# NB2_PBCON.net
KiCad netlist of a schematic drawn in Altium Designer
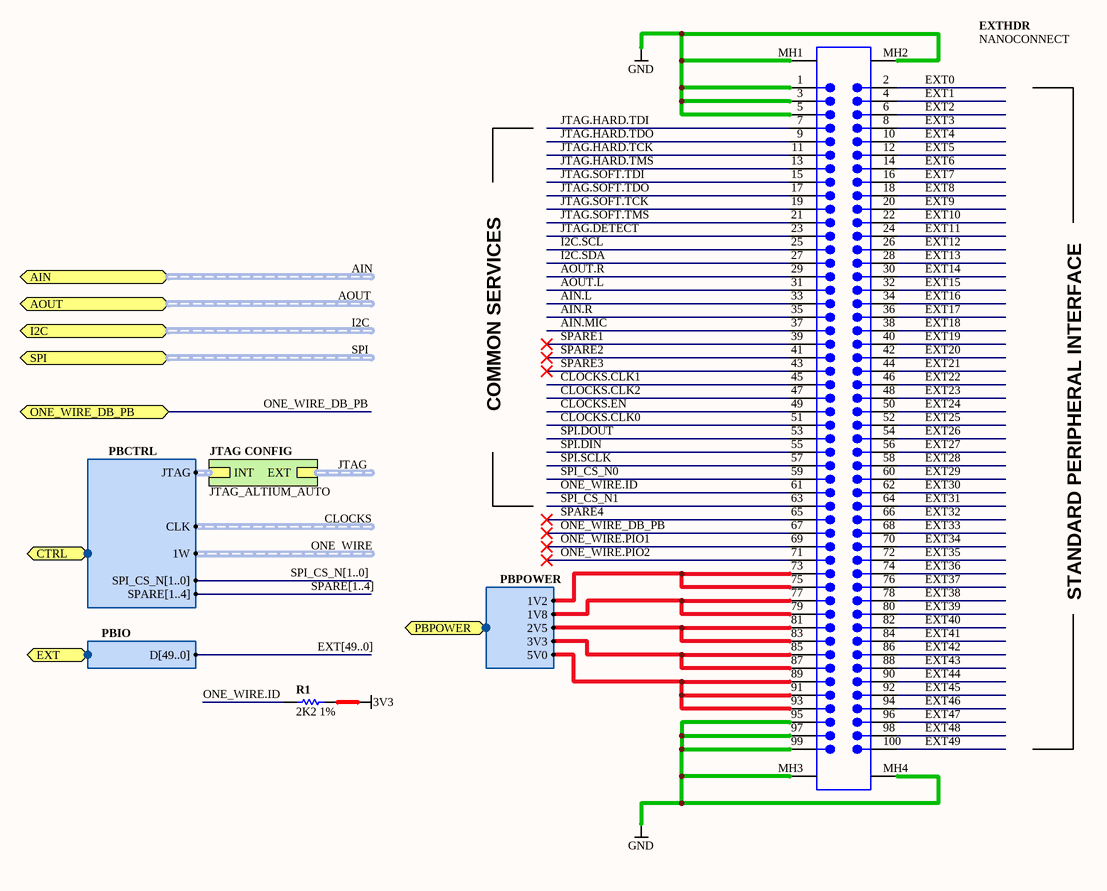
[diagram p0: NB2_PBCON.schdoc]

(export (version "E")
  (design (tool "Eeschema 10.0.6"))
  (components
    (comp (ref "EXTHDR")
      (value "NANOCONNECT")
      (footprint "53751")
      (description "Connector, Molex Docking Station 100 Pin Female 53751")
      (libsource (lib "altium-import") (part "root_0_CON-DOCKSTAT-100-F-STR_"))
    )
    (comp (ref "R1")
      (value "2K2 1%")
      (footprint "RESC1005-STAR")
      (description "Resistor, 2K2 1% 0402 (1005)")
      (fields (field (name "TOLERANCE") "1 %"))
      (libsource (lib "AltiumDesignLibrary") (part "RES"))
    )
  )
  (nets
    (net (code "11") (name "/AIN.L") (class "Default")
      (node (ref "EXTHDR") (pin "33") (pinfunction "33_33") (pintype "passive"))
    )
    (net (code "12") (name "/AIN.MIC") (class "Default")
      (node (ref "EXTHDR") (pin "37") (pinfunction "37_37") (pintype "passive"))
    )
    (net (code "13") (name "/AIN.R") (class "Default")
      (node (ref "EXTHDR") (pin "35") (pinfunction "35_35") (pintype "passive"))
    )
    (net (code "14") (name "/AOUT.L") (class "Default")
      (node (ref "EXTHDR") (pin "31") (pinfunction "31_31") (pintype "passive"))
    )
    (net (code "15") (name "/AOUT.R") (class "Default")
      (node (ref "EXTHDR") (pin "29") (pinfunction "29_29") (pintype "passive"))
    )
    (net (code "16") (name "/CLOCKS.CLK0") (class "Default")
      (node (ref "EXTHDR") (pin "51") (pinfunction "51_51") (pintype "passive"))
    )
    (net (code "17") (name "/CLOCKS.CLK1") (class "Default")
      (node (ref "EXTHDR") (pin "45") (pinfunction "45_45") (pintype "passive"))
    )
    (net (code "18") (name "/CLOCKS.CLK2") (class "Default")
      (node (ref "EXTHDR") (pin "47") (pinfunction "47_47") (pintype "passive"))
    )
    (net (code "19") (name "/CLOCKS.EN") (class "Default")
      (node (ref "EXTHDR") (pin "49") (pinfunction "49_49") (pintype "passive"))
    )
    (net (code "21") (name "/EXT0") (class "Default")
      (node (ref "EXTHDR") (pin "2") (pinfunction "2_2") (pintype "passive"))
    )
    (net (code "22") (name "/EXT1") (class "Default")
      (node (ref "EXTHDR") (pin "4") (pinfunction "4_4") (pintype "passive"))
    )
    (net (code "23") (name "/EXT2") (class "Default")
      (node (ref "EXTHDR") (pin "6") (pinfunction "6_6") (pintype "passive"))
    )
    (net (code "24") (name "/EXT3") (class "Default")
      (node (ref "EXTHDR") (pin "8") (pinfunction "8_8") (pintype "passive"))
    )
    (net (code "25") (name "/EXT4") (class "Default")
      (node (ref "EXTHDR") (pin "10") (pinfunction "10_10") (pintype "passive"))
    )
    (net (code "26") (name "/EXT5") (class "Default")
      (node (ref "EXTHDR") (pin "12") (pinfunction "12_12") (pintype "passive"))
    )
    (net (code "27") (name "/EXT6") (class "Default")
      (node (ref "EXTHDR") (pin "14") (pinfunction "14_14") (pintype "passive"))
    )
    (net (code "28") (name "/EXT7") (class "Default")
      (node (ref "EXTHDR") (pin "16") (pinfunction "16_16") (pintype "passive"))
    )
    (net (code "29") (name "/EXT8") (class "Default")
      (node (ref "EXTHDR") (pin "18") (pinfunction "18_18") (pintype "passive"))
    )
    (net (code "30") (name "/EXT9") (class "Default")
      (node (ref "EXTHDR") (pin "20") (pinfunction "20_20") (pintype "passive"))
    )
    (net (code "31") (name "/EXT10") (class "Default")
      (node (ref "EXTHDR") (pin "22") (pinfunction "22_22") (pintype "passive"))
    )
    (net (code "32") (name "/EXT11") (class "Default")
      (node (ref "EXTHDR") (pin "24") (pinfunction "24_24") (pintype "passive"))
    )
    (net (code "33") (name "/EXT12") (class "Default")
      (node (ref "EXTHDR") (pin "26") (pinfunction "26_26") (pintype "passive"))
    )
    (net (code "34") (name "/EXT13") (class "Default")
      (node (ref "EXTHDR") (pin "28") (pinfunction "28_28") (pintype "passive"))
    )
    (net (code "35") (name "/EXT14") (class "Default")
      (node (ref "EXTHDR") (pin "30") (pinfunction "30_30") (pintype "passive"))
    )
    (net (code "36") (name "/EXT15") (class "Default")
      (node (ref "EXTHDR") (pin "32") (pinfunction "32_32") (pintype "passive"))
    )
    (net (code "37") (name "/EXT16") (class "Default")
      (node (ref "EXTHDR") (pin "34") (pinfunction "34_34") (pintype "passive"))
    )
    (net (code "38") (name "/EXT17") (class "Default")
      (node (ref "EXTHDR") (pin "36") (pinfunction "36_36") (pintype "passive"))
    )
    (net (code "39") (name "/EXT18") (class "Default")
      (node (ref "EXTHDR") (pin "38") (pinfunction "38_38") (pintype "passive"))
    )
    (net (code "40") (name "/EXT19") (class "Default")
      (node (ref "EXTHDR") (pin "40") (pinfunction "40_40") (pintype "passive"))
    )
    (net (code "41") (name "/EXT20") (class "Default")
      (node (ref "EXTHDR") (pin "42") (pinfunction "42_42") (pintype "passive"))
    )
    (net (code "42") (name "/EXT21") (class "Default")
      (node (ref "EXTHDR") (pin "44") (pinfunction "44_44") (pintype "passive"))
    )
    (net (code "43") (name "/EXT22") (class "Default")
      (node (ref "EXTHDR") (pin "46") (pinfunction "46_46") (pintype "passive"))
    )
    (net (code "44") (name "/EXT23") (class "Default")
      (node (ref "EXTHDR") (pin "48") (pinfunction "48_48") (pintype "passive"))
    )
    (net (code "45") (name "/EXT24") (class "Default")
      (node (ref "EXTHDR") (pin "50") (pinfunction "50_50") (pintype "passive"))
    )
    (net (code "46") (name "/EXT25") (class "Default")
      (node (ref "EXTHDR") (pin "52") (pinfunction "52_52") (pintype "passive"))
    )
    (net (code "47") (name "/EXT26") (class "Default")
      (node (ref "EXTHDR") (pin "54") (pinfunction "54_54") (pintype "passive"))
    )
    (net (code "48") (name "/EXT27") (class "Default")
      (node (ref "EXTHDR") (pin "56") (pinfunction "56_56") (pintype "passive"))
    )
    (net (code "49") (name "/EXT28") (class "Default")
      (node (ref "EXTHDR") (pin "58") (pinfunction "58_58") (pintype "passive"))
    )
    (net (code "50") (name "/EXT29") (class "Default")
      (node (ref "EXTHDR") (pin "60") (pinfunction "60_60") (pintype "passive"))
    )
    (net (code "51") (name "/EXT30") (class "Default")
      (node (ref "EXTHDR") (pin "62") (pinfunction "62_62") (pintype "passive"))
    )
    (net (code "52") (name "/EXT31") (class "Default")
      (node (ref "EXTHDR") (pin "64") (pinfunction "64_64") (pintype "passive"))
    )
    (net (code "53") (name "/EXT32") (class "Default")
      (node (ref "EXTHDR") (pin "66") (pinfunction "66_66") (pintype "passive"))
    )
    (net (code "54") (name "/EXT33") (class "Default")
      (node (ref "EXTHDR") (pin "68") (pinfunction "68_68") (pintype "passive"))
    )
    (net (code "55") (name "/EXT34") (class "Default")
      (node (ref "EXTHDR") (pin "70") (pinfunction "70_70") (pintype "passive"))
    )
    (net (code "56") (name "/EXT35") (class "Default")
      (node (ref "EXTHDR") (pin "72") (pinfunction "72_72") (pintype "passive"))
    )
    (net (code "57") (name "/EXT36") (class "Default")
      (node (ref "EXTHDR") (pin "74") (pinfunction "74_74") (pintype "passive"))
    )
    (net (code "58") (name "/EXT37") (class "Default")
      (node (ref "EXTHDR") (pin "76") (pinfunction "76_76") (pintype "passive"))
    )
    (net (code "59") (name "/EXT38") (class "Default")
      (node (ref "EXTHDR") (pin "78") (pinfunction "78_78") (pintype "passive"))
    )
    (net (code "60") (name "/EXT39") (class "Default")
      (node (ref "EXTHDR") (pin "80") (pinfunction "80_80") (pintype "passive"))
    )
    (net (code "61") (name "/EXT40") (class "Default")
      (node (ref "EXTHDR") (pin "82") (pinfunction "82_82") (pintype "passive"))
    )
    (net (code "62") (name "/EXT41") (class "Default")
      (node (ref "EXTHDR") (pin "84") (pinfunction "84_84") (pintype "passive"))
    )
    (net (code "63") (name "/EXT42") (class "Default")
      (node (ref "EXTHDR") (pin "86") (pinfunction "86_86") (pintype "passive"))
    )
    (net (code "64") (name "/EXT43") (class "Default")
      (node (ref "EXTHDR") (pin "88") (pinfunction "88_88") (pintype "passive"))
    )
    (net (code "65") (name "/EXT44") (class "Default")
      (node (ref "EXTHDR") (pin "90") (pinfunction "90_90") (pintype "passive"))
    )
    (net (code "66") (name "/EXT45") (class "Default")
      (node (ref "EXTHDR") (pin "92") (pinfunction "92_92") (pintype "passive"))
    )
    (net (code "67") (name "/EXT46") (class "Default")
      (node (ref "EXTHDR") (pin "94") (pinfunction "94_94") (pintype "passive"))
    )
    (net (code "68") (name "/EXT47") (class "Default")
      (node (ref "EXTHDR") (pin "96") (pinfunction "96_96") (pintype "passive"))
    )
    (net (code "69") (name "/EXT48") (class "Default")
      (node (ref "EXTHDR") (pin "98") (pinfunction "98_98") (pintype "passive"))
    )
    (net (code "70") (name "/EXT49") (class "Default")
      (node (ref "EXTHDR") (pin "100") (pinfunction "100_100") (pintype "passive"))
    )
    (net (code "72") (name "/I2C.SCL") (class "Default")
      (node (ref "EXTHDR") (pin "25") (pinfunction "25_25") (pintype "passive"))
    )
    (net (code "73") (name "/I2C.SDA") (class "Default")
      (node (ref "EXTHDR") (pin "27") (pinfunction "27_27") (pintype "passive"))
    )
    (net (code "75") (name "/JTAG.DETECT") (class "Default")
      (node (ref "EXTHDR") (pin "23") (pinfunction "23_23") (pintype "passive"))
    )
    (net (code "76") (name "/JTAG.HARD.TCK") (class "Default")
      (node (ref "EXTHDR") (pin "11") (pinfunction "11_11") (pintype "passive"))
    )
    (net (code "77") (name "/JTAG.HARD.TDI") (class "Default")
      (node (ref "EXTHDR") (pin "7") (pinfunction "7_7") (pintype "passive"))
    )
    (net (code "78") (name "/JTAG.HARD.TDO") (class "Default")
      (node (ref "EXTHDR") (pin "9") (pinfunction "9_9") (pintype "passive"))
    )
    (net (code "79") (name "/JTAG.HARD.TMS") (class "Default")
      (node (ref "EXTHDR") (pin "13") (pinfunction "13_13") (pintype "passive"))
    )
    (net (code "80") (name "/JTAG.SOFT.TCK") (class "Default")
      (node (ref "EXTHDR") (pin "19") (pinfunction "19_19") (pintype "passive"))
    )
    (net (code "81") (name "/JTAG.SOFT.TDI") (class "Default")
      (node (ref "EXTHDR") (pin "15") (pinfunction "15_15") (pintype "passive"))
    )
    (net (code "82") (name "/JTAG.SOFT.TDO") (class "Default")
      (node (ref "EXTHDR") (pin "17") (pinfunction "17_17") (pintype "passive"))
    )
    (net (code "83") (name "/JTAG.SOFT.TMS") (class "Default")
      (node (ref "EXTHDR") (pin "21") (pinfunction "21_21") (pintype "passive"))
    )
    (net (code "84") (name "/ONE_WIRE.ID") (class "Default")
      (node (ref "EXTHDR") (pin "61") (pinfunction "61_61") (pintype "passive"))
      (node (ref "R1") (pin "1") (pinfunction "1_1") (pintype "passive"))
    )
    (net (code "85") (name "/ONE_WIRE.PIO1") (class "Default")
      (node (ref "EXTHDR") (pin "69") (pinfunction "69_69") (pintype "passive+no_connect"))
    )
    (net (code "86") (name "/ONE_WIRE.PIO2") (class "Default")
      (node (ref "EXTHDR") (pin "71") (pinfunction "71_71") (pintype "passive+no_connect"))
    )
    (net (code "87") (name "/ONE_WIRE_DB_PB") (class "Default")
      (node (ref "EXTHDR") (pin "67") (pinfunction "67_67") (pintype "passive+no_connect"))
    )
    (net (code "88") (name "/SPARE1") (class "Default")
      (node (ref "EXTHDR") (pin "39") (pinfunction "39_39") (pintype "passive+no_connect"))
    )
    (net (code "89") (name "/SPARE2") (class "Default")
      (node (ref "EXTHDR") (pin "41") (pinfunction "41_41") (pintype "passive+no_connect"))
    )
    (net (code "90") (name "/SPARE3") (class "Default")
      (node (ref "EXTHDR") (pin "43") (pinfunction "43_43") (pintype "passive+no_connect"))
    )
    (net (code "91") (name "/SPARE4") (class "Default")
      (node (ref "EXTHDR") (pin "65") (pinfunction "65_65") (pintype "passive+no_connect"))
    )
    (net (code "92") (name "/SPI.DIN") (class "Default")
      (node (ref "EXTHDR") (pin "55") (pinfunction "55_55") (pintype "passive"))
    )
    (net (code "93") (name "/SPI.DOUT") (class "Default")
      (node (ref "EXTHDR") (pin "53") (pinfunction "53_53") (pintype "passive"))
    )
    (net (code "94") (name "/SPI.SCLK") (class "Default")
      (node (ref "EXTHDR") (pin "57") (pinfunction "57_57") (pintype "passive"))
    )
    (net (code "95") (name "/SPI_CS_N0") (class "Default")
      (node (ref "EXTHDR") (pin "59") (pinfunction "59_59") (pintype "passive"))
    )
    (net (code "96") (name "/SPI_CS_N1") (class "Default")
      (node (ref "EXTHDR") (pin "63") (pinfunction "63_63") (pintype "passive"))
    )
    (net (code "107") (name "3V3") (class "Default")
      (node (ref "R1") (pin "2") (pinfunction "2_2") (pintype "passive"))
    )
    (net (code "108") (name "GND") (class "Default")
      (node (ref "EXTHDR") (pin "1") (pinfunction "1_1") (pintype "passive"))
      (node (ref "EXTHDR") (pin "3") (pinfunction "3_3") (pintype "passive"))
      (node (ref "EXTHDR") (pin "5") (pinfunction "5_5") (pintype "passive"))
      (node (ref "EXTHDR") (pin "95") (pinfunction "95_95") (pintype "passive"))
      (node (ref "EXTHDR") (pin "97") (pinfunction "97_97") (pintype "passive"))
      (node (ref "EXTHDR") (pin "99") (pinfunction "99_99") (pintype "passive"))
      (node (ref "EXTHDR") (pin "MH1") (pinfunction "MH1_MH1") (pintype "passive"))
      (node (ref "EXTHDR") (pin "MH2") (pinfunction "MH2_MH2") (pintype "passive"))
      (node (ref "EXTHDR") (pin "MH3") (pinfunction "MH3_MH3") (pintype "passive"))
      (node (ref "EXTHDR") (pin "MH4") (pinfunction "MH4_MH4") (pintype "passive"))
    )
    (net (code "109") (name "Net-(EXTHDR-Pad73)") (class "Default")
      (node (ref "EXTHDR") (pin "73") (pinfunction "73_73") (pintype "passive"))
      (node (ref "EXTHDR") (pin "75") (pinfunction "75_75") (pintype "passive"))
    )
    (net (code "110") (name "Net-(EXTHDR-Pad77)") (class "Default")
      (node (ref "EXTHDR") (pin "77") (pinfunction "77_77") (pintype "passive"))
      (node (ref "EXTHDR") (pin "79") (pinfunction "79_79") (pintype "passive"))
    )
    (net (code "111") (name "Net-(EXTHDR-Pad81)") (class "Default")
      (node (ref "EXTHDR") (pin "81") (pinfunction "81_81") (pintype "passive"))
      (node (ref "EXTHDR") (pin "83") (pinfunction "83_83") (pintype "passive"))
    )
    (net (code "112") (name "Net-(EXTHDR-Pad85)") (class "Default")
      (node (ref "EXTHDR") (pin "85") (pinfunction "85_85") (pintype "passive"))
      (node (ref "EXTHDR") (pin "87") (pinfunction "87_87") (pintype "passive"))
    )
    (net (code "113") (name "Net-(EXTHDR-Pad89)") (class "Default")
      (node (ref "EXTHDR") (pin "89") (pinfunction "89_89") (pintype "passive"))
      (node (ref "EXTHDR") (pin "91") (pinfunction "91_91") (pintype "passive"))
      (node (ref "EXTHDR") (pin "93") (pinfunction "93_93") (pintype "passive"))
    )
  )
)
